# QUTMS-TSAL-S04.net
KiCad netlist of a schematic drawn in Altium Designer
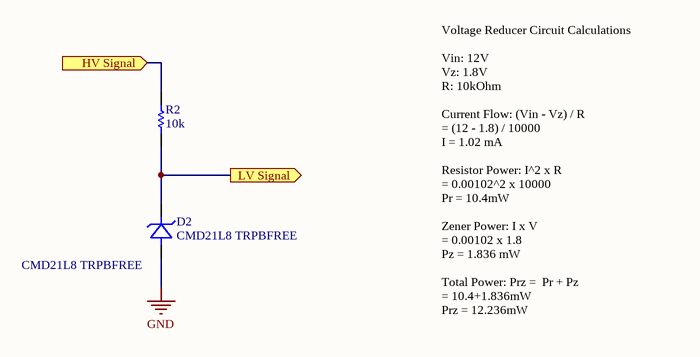
[diagram p0: QUTMS-TSAL-S04.SchDoc]

(export (version "E")
  (design (tool "Eeschema 10.0.6"))
  (components
    (comp (ref "D2")
      (value "CMD21L8 TRPBFREE")
      (footprint "SODFL160X80-2N")
      (libsource (lib "QUTMS_DiodeLibrary") (part "CMD21L8 TRPBFREE"))
    )
    (comp (ref "R2")
      (value "10k")
      (footprint "Res_ThinFilm_0603")
      (description "Resistor, SMD, 10k, 0.1W, 5%, 0603")
      (libsource (lib "StandardResistors") (part "10k 5% 0603"))
    )
  )
  (nets
    (net (code "1") (name "/HV Signal") (class "Default")
      (node (ref "R2") (pin "2") (pinfunction "2_2") (pintype "passive"))
    )
    (net (code "2") (name "/LV Signal") (class "Default")
      (node (ref "D2") (pin "K") (pinfunction "Cathode_K") (pintype "passive"))
      (node (ref "R2") (pin "1") (pinfunction "1_1") (pintype "passive"))
    )
    (net (code "3") (name "GND") (class "Default")
      (node (ref "D2") (pin "A") (pinfunction "Anode_A") (pintype "passive"))
    )
  )
)
